# BigBus_Error_rev2.net
KiCad netlist of a schematic drawn in EAGLE
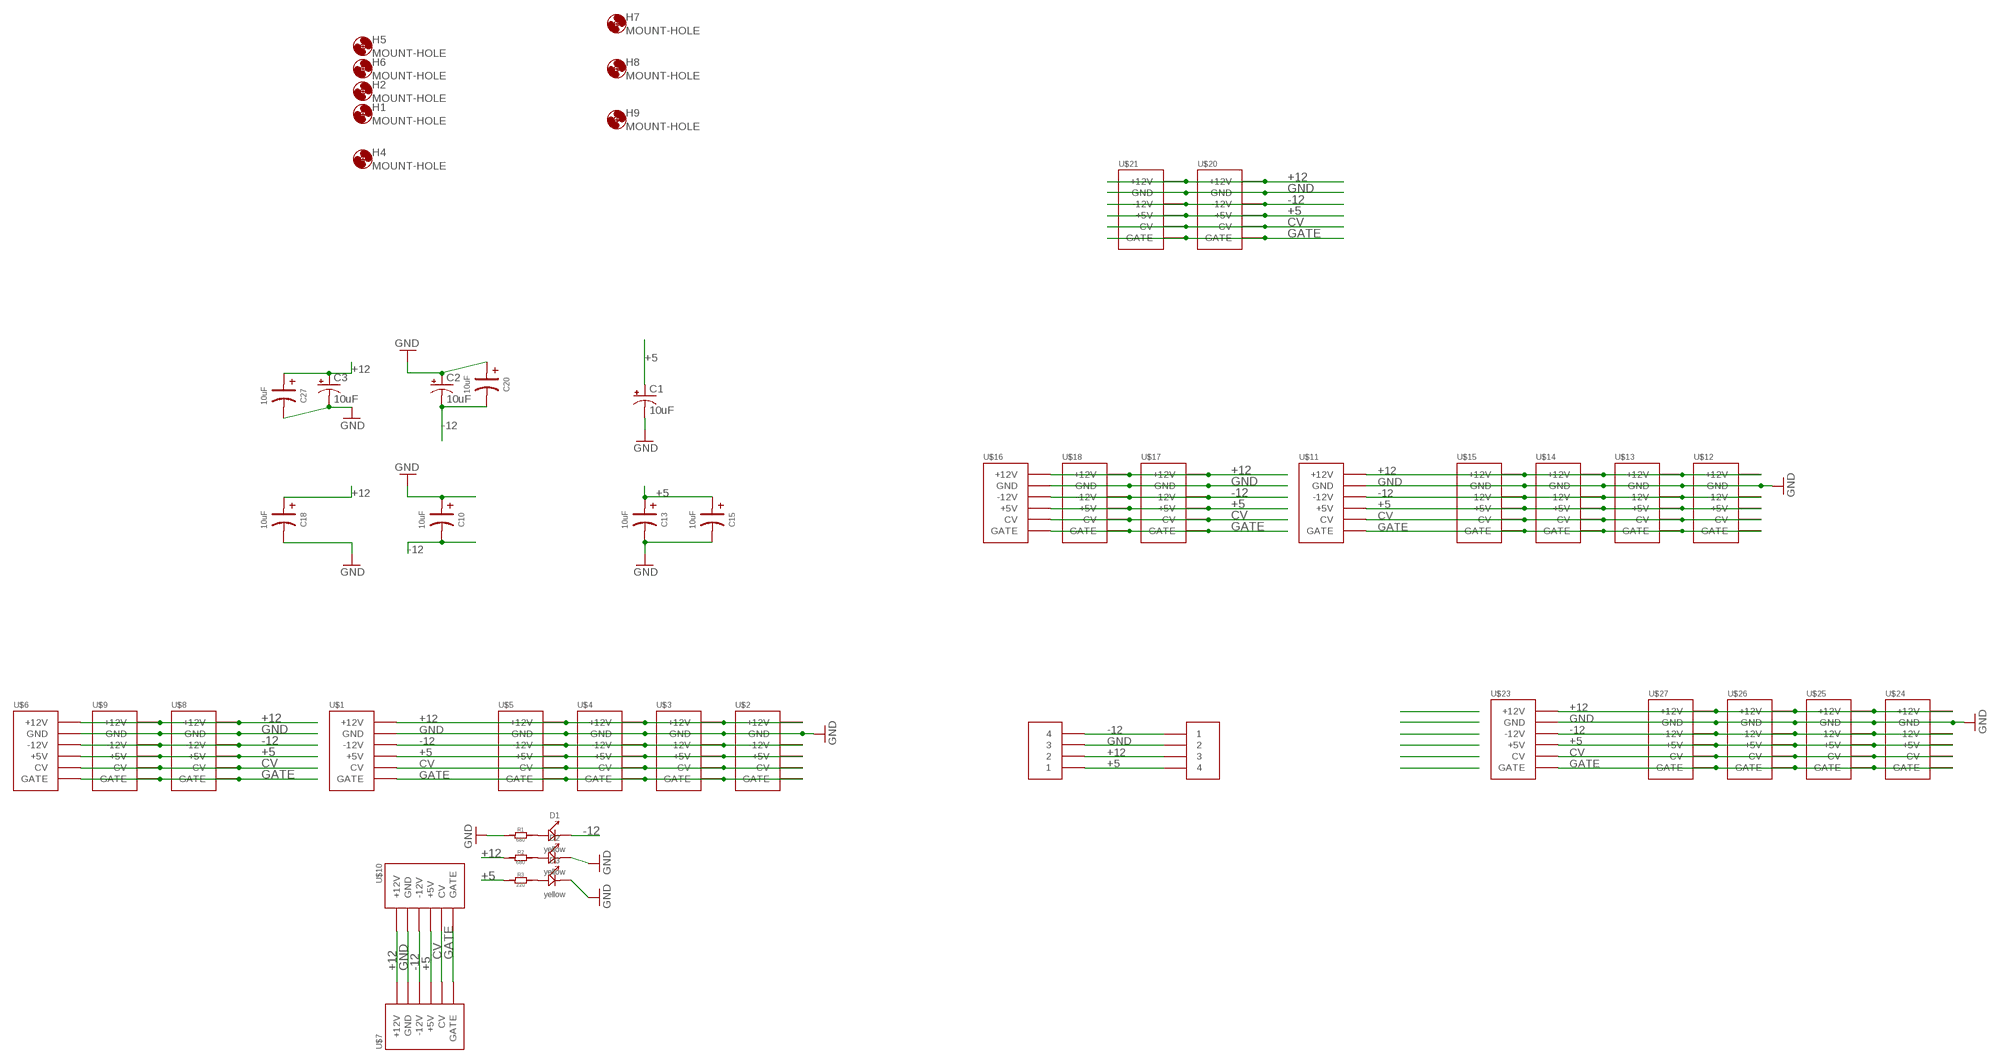
[diagram p0: schematic, sheet 1]

(export (version "E")
  (design (tool "Eeschema 10.0.6"))
  (components
    (comp (ref "C1")
      (value "10uF")
      (footprint "eagle-import:PANASONIC_D")
      (libsource (lib "eagle-import") (part "CAP_POLD"))
    )
    (comp (ref "C2")
      (value "10uF")
      (footprint "eagle-import:PANASONIC_D")
      (libsource (lib "eagle-import") (part "CAP_POLD"))
    )
    (comp (ref "C3")
      (value "10uF")
      (footprint "eagle-import:PANASONIC_D")
      (libsource (lib "eagle-import") (part "CAP_POLD"))
    )
    (comp (ref "C10")
      (value "10uF")
      (footprint "eagle-import:CASE-A_3216")
      (libsource (lib "eagle-import") (part "C-POLAR-A"))
    )
    (comp (ref "C13")
      (value "10uF")
      (footprint "eagle-import:CASE-A_3216")
      (libsource (lib "eagle-import") (part "C-POLAR-A"))
    )
    (comp (ref "C15")
      (value "10uF")
      (footprint "eagle-import:CASE-A_3216")
      (libsource (lib "eagle-import") (part "C-POLAR-A"))
    )
    (comp (ref "C18")
      (value "10uF")
      (footprint "eagle-import:CASE-A_3216")
      (libsource (lib "eagle-import") (part "C-POLAR-A"))
    )
    (comp (ref "C20")
      (value "10uF")
      (footprint "eagle-import:CASE-A_3216")
      (libsource (lib "eagle-import") (part "C-POLAR-A"))
    )
    (comp (ref "C27")
      (value "10uF")
      (footprint "eagle-import:CASE-A_3216")
      (libsource (lib "eagle-import") (part "C-POLAR-A"))
    )
    (comp (ref "D1")
      (value "yellow")
      (footprint "eagle-import:LED0603")
      (libsource (lib "eagle-import") (part "LED"))
    )
    (comp (ref "D2")
      (value "yellow")
      (footprint "eagle-import:LED0603")
      (libsource (lib "eagle-import") (part "LED"))
    )
    (comp (ref "D3")
      (value "yellow")
      (footprint "eagle-import:LED0603")
      (libsource (lib "eagle-import") (part "LED"))
    )
    (comp (ref "H1")
      (value "MOUNT-HOLE")
      (footprint "eagle-import:3.2-NOMARKINGS-SMALLSAFEZONE")
      (libsource (lib "eagle-import") (part "MOUNT-HOLE"))
    )
    (comp (ref "H2")
      (value "MOUNT-HOLE")
      (footprint "eagle-import:3.2-NOMARKINGS-SMALLSAFEZONE")
      (libsource (lib "eagle-import") (part "MOUNT-HOLE"))
    )
    (comp (ref "H4")
      (value "MOUNT-HOLE")
      (footprint "eagle-import:3.2-NOMARKINGS-SMALLSAFEZONE")
      (libsource (lib "eagle-import") (part "MOUNT-HOLE"))
    )
    (comp (ref "H5")
      (value "MOUNT-HOLE")
      (footprint "eagle-import:3.2-NOMARKINGS-SMALLSAFEZONE")
      (libsource (lib "eagle-import") (part "MOUNT-HOLE"))
    )
    (comp (ref "H6")
      (value "MOUNT-HOLE")
      (footprint "eagle-import:3.2-NOMARKINGS-SMALLSAFEZONE")
      (libsource (lib "eagle-import") (part "MOUNT-HOLE"))
    )
    (comp (ref "H7")
      (value "MOUNT-HOLE")
      (footprint "eagle-import:3.2-NOMARKINGS-SMALLSAFEZONE")
      (libsource (lib "eagle-import") (part "MOUNT-HOLE"))
    )
    (comp (ref "H8")
      (value "MOUNT-HOLE")
      (footprint "eagle-import:3.2-NOMARKINGS-SMALLSAFEZONE")
      (libsource (lib "eagle-import") (part "MOUNT-HOLE"))
    )
    (comp (ref "H9")
      (value "MOUNT-HOLE")
      (footprint "eagle-import:3.2-NOMARKINGS-SMALLSAFEZONE")
      (libsource (lib "eagle-import") (part "MOUNT-HOLE"))
    )
    (comp (ref "R1")
      (value "680")
      (footprint "eagle-import:R0603")
      (libsource (lib "eagle-import") (part "R-0603"))
    )
    (comp (ref "R2")
      (value "680")
      (footprint "eagle-import:R0603")
      (libsource (lib "eagle-import") (part "R-0603"))
    )
    (comp (ref "R3")
      (value "220")
      (footprint "eagle-import:R0603")
      (libsource (lib "eagle-import") (part "R-0603"))
    )
    (comp (ref "U$1")
      (value "POWER_SHROUDED_NOTEXT")
      (footprint "eagle-import:POWER_16_SHROUDED_NOTEXT")
      (libsource (lib "eagle-import") (part "POWER_SHROUDED_NOTEXT"))
    )
    (comp (ref "U$2")
      (value "POWER_SHROUDED_NOTEXT")
      (footprint "eagle-import:POWER_16_SHROUDED_NOTEXT")
      (libsource (lib "eagle-import") (part "POWER_SHROUDED_NOTEXT"))
    )
    (comp (ref "U$3")
      (value "POWER_SHROUDED_NOTEXT")
      (footprint "eagle-import:POWER_16_SHROUDED_NOTEXT")
      (libsource (lib "eagle-import") (part "POWER_SHROUDED_NOTEXT"))
    )
    (comp (ref "U$4")
      (value "POWER_SHROUDED_NOTEXT")
      (footprint "eagle-import:POWER_16_SHROUDED_NOTEXT")
      (libsource (lib "eagle-import") (part "POWER_SHROUDED_NOTEXT"))
    )
    (comp (ref "U$5")
      (value "POWER_SHROUDED_NOTEXT")
      (footprint "eagle-import:POWER_16_SHROUDED_NOTEXT")
      (libsource (lib "eagle-import") (part "POWER_SHROUDED_NOTEXT"))
    )
    (comp (ref "U$6")
      (value "POWER_SHROUDED_NOTEXT")
      (footprint "eagle-import:POWER_16_SHROUDED_NOTEXT")
      (libsource (lib "eagle-import") (part "POWER_SHROUDED_NOTEXT"))
    )
    (comp (ref "U$7")
      (value "POWER_SHROUDED_NOTEXT")
      (footprint "eagle-import:POWER_16_SHROUDED_NOTEXT")
      (libsource (lib "eagle-import") (part "POWER_SHROUDED_NOTEXT"))
    )
    (comp (ref "U$8")
      (value "POWER_SHROUDED_NOTEXT")
      (footprint "eagle-import:POWER_16_SHROUDED_NOTEXT")
      (libsource (lib "eagle-import") (part "POWER_SHROUDED_NOTEXT"))
    )
    (comp (ref "U$9")
      (value "POWER_SHROUDED_NOTEXT")
      (footprint "eagle-import:POWER_16_SHROUDED_NOTEXT")
      (libsource (lib "eagle-import") (part "POWER_SHROUDED_NOTEXT"))
    )
    (comp (ref "U$10")
      (value "POWER_SHROUDED_NOTEXT")
      (footprint "eagle-import:POWER_16_SHROUDED_NOTEXT")
      (libsource (lib "eagle-import") (part "POWER_SHROUDED_NOTEXT"))
    )
    (comp (ref "U$11")
      (value "POWER_SHROUDED_NOTEXT")
      (footprint "eagle-import:POWER_16_SHROUDED_NOTEXT")
      (libsource (lib "eagle-import") (part "POWER_SHROUDED_NOTEXT"))
    )
    (comp (ref "U$12")
      (value "POWER_SHROUDED_NOTEXT")
      (footprint "eagle-import:POWER_16_SHROUDED_NOTEXT")
      (libsource (lib "eagle-import") (part "POWER_SHROUDED_NOTEXT"))
    )
    (comp (ref "U$13")
      (value "POWER_SHROUDED_NOTEXT")
      (footprint "eagle-import:POWER_16_SHROUDED_NOTEXT")
      (libsource (lib "eagle-import") (part "POWER_SHROUDED_NOTEXT"))
    )
    (comp (ref "U$14")
      (value "POWER_SHROUDED_NOTEXT")
      (footprint "eagle-import:POWER_16_SHROUDED_NOTEXT")
      (libsource (lib "eagle-import") (part "POWER_SHROUDED_NOTEXT"))
    )
    (comp (ref "U$15")
      (value "POWER_SHROUDED_NOTEXT")
      (footprint "eagle-import:POWER_16_SHROUDED_NOTEXT")
      (libsource (lib "eagle-import") (part "POWER_SHROUDED_NOTEXT"))
    )
    (comp (ref "U$16")
      (value "POWER_SHROUDED_NOTEXT")
      (footprint "eagle-import:POWER_16_SHROUDED_NOTEXT")
      (libsource (lib "eagle-import") (part "POWER_SHROUDED_NOTEXT"))
    )
    (comp (ref "U$17")
      (value "POWER_SHROUDED_NOTEXT")
      (footprint "eagle-import:POWER_16_SHROUDED_NOTEXT")
      (libsource (lib "eagle-import") (part "POWER_SHROUDED_NOTEXT"))
    )
    (comp (ref "U$18")
      (value "POWER_SHROUDED_NOTEXT")
      (footprint "eagle-import:POWER_16_SHROUDED_NOTEXT")
      (libsource (lib "eagle-import") (part "POWER_SHROUDED_NOTEXT"))
    )
    (comp (ref "U$19")
      (value "4PIN5MM")
      (footprint "eagle-import:4PIN5MM")
      (libsource (lib "eagle-import") (part "4PIN5MM"))
    )
    (comp (ref "U$20")
      (value "POWER_SHROUDED_NOTEXT")
      (footprint "eagle-import:POWER_16_SHROUDED_NOTEXT")
      (libsource (lib "eagle-import") (part "POWER_SHROUDED_NOTEXT"))
    )
    (comp (ref "U$21")
      (value "POWER_SHROUDED_NOTEXT")
      (footprint "eagle-import:POWER_16_SHROUDED_NOTEXT")
      (libsource (lib "eagle-import") (part "POWER_SHROUDED_NOTEXT"))
    )
    (comp (ref "U$22")
      (value "4PIN5MM")
      (footprint "eagle-import:4PIN5MM")
      (libsource (lib "eagle-import") (part "4PIN5MM"))
    )
    (comp (ref "U$23")
      (value "POWER_SHROUDED_NOTEXT")
      (footprint "eagle-import:POWER_16_SHROUDED_NOTEXT")
      (libsource (lib "eagle-import") (part "POWER_SHROUDED_NOTEXT"))
    )
    (comp (ref "U$24")
      (value "POWER_SHROUDED_NOTEXT")
      (footprint "eagle-import:POWER_16_SHROUDED_NOTEXT")
      (libsource (lib "eagle-import") (part "POWER_SHROUDED_NOTEXT"))
    )
    (comp (ref "U$25")
      (value "POWER_SHROUDED_NOTEXT")
      (footprint "eagle-import:POWER_16_SHROUDED_NOTEXT")
      (libsource (lib "eagle-import") (part "POWER_SHROUDED_NOTEXT"))
    )
    (comp (ref "U$26")
      (value "POWER_SHROUDED_NOTEXT")
      (footprint "eagle-import:POWER_16_SHROUDED_NOTEXT")
      (libsource (lib "eagle-import") (part "POWER_SHROUDED_NOTEXT"))
    )
    (comp (ref "U$27")
      (value "POWER_SHROUDED_NOTEXT")
      (footprint "eagle-import:POWER_16_SHROUDED_NOTEXT")
      (libsource (lib "eagle-import") (part "POWER_SHROUDED_NOTEXT"))
    )
  )
  (nets
    (net (code "1") (name "/+5") (class "Default")
      (node (ref "C1") (pin "+") (pinfunction "+_+") (pintype "passive"))
      (node (ref "C13") (pin "+") (pinfunction "1_+") (pintype "bidirectional"))
      (node (ref "C15") (pin "+") (pinfunction "1_+") (pintype "bidirectional"))
      (node (ref "R3") (pin "1") (pinfunction "1_1") (pintype "bidirectional"))
      (node (ref "U$1") (pin "11") (pinfunction "+5V_11") (pintype "bidirectional"))
      (node (ref "U$1") (pin "12") (pinfunction "+5V_12") (pintype "bidirectional"))
      (node (ref "U$10") (pin "11") (pinfunction "+5V_11") (pintype "bidirectional"))
      (node (ref "U$10") (pin "12") (pinfunction "+5V_12") (pintype "bidirectional"))
      (node (ref "U$11") (pin "11") (pinfunction "+5V_11") (pintype "bidirectional"))
      (node (ref "U$11") (pin "12") (pinfunction "+5V_12") (pintype "bidirectional"))
      (node (ref "U$12") (pin "11") (pinfunction "+5V_11") (pintype "bidirectional"))
      (node (ref "U$12") (pin "12") (pinfunction "+5V_12") (pintype "bidirectional"))
      (node (ref "U$13") (pin "11") (pinfunction "+5V_11") (pintype "bidirectional"))
      (node (ref "U$13") (pin "12") (pinfunction "+5V_12") (pintype "bidirectional"))
      (node (ref "U$14") (pin "11") (pinfunction "+5V_11") (pintype "bidirectional"))
      (node (ref "U$14") (pin "12") (pinfunction "+5V_12") (pintype "bidirectional"))
      (node (ref "U$15") (pin "11") (pinfunction "+5V_11") (pintype "bidirectional"))
      (node (ref "U$15") (pin "12") (pinfunction "+5V_12") (pintype "bidirectional"))
      (node (ref "U$16") (pin "11") (pinfunction "+5V_11") (pintype "bidirectional"))
      (node (ref "U$16") (pin "12") (pinfunction "+5V_12") (pintype "bidirectional"))
      (node (ref "U$17") (pin "11") (pinfunction "+5V_11") (pintype "bidirectional"))
      (node (ref "U$17") (pin "12") (pinfunction "+5V_12") (pintype "bidirectional"))
      (node (ref "U$18") (pin "11") (pinfunction "+5V_11") (pintype "bidirectional"))
      (node (ref "U$18") (pin "12") (pinfunction "+5V_12") (pintype "bidirectional"))
      (node (ref "U$19") (pin "4") (pinfunction "4_4") (pintype "bidirectional"))
      (node (ref "U$2") (pin "11") (pinfunction "+5V_11") (pintype "bidirectional"))
      (node (ref "U$2") (pin "12") (pinfunction "+5V_12") (pintype "bidirectional"))
      (node (ref "U$20") (pin "11") (pinfunction "+5V_11") (pintype "bidirectional"))
      (node (ref "U$20") (pin "12") (pinfunction "+5V_12") (pintype "bidirectional"))
      (node (ref "U$21") (pin "11") (pinfunction "+5V_11") (pintype "bidirectional"))
      (node (ref "U$21") (pin "12") (pinfunction "+5V_12") (pintype "bidirectional"))
      (node (ref "U$22") (pin "1") (pinfunction "1_1") (pintype "bidirectional"))
      (node (ref "U$23") (pin "11") (pinfunction "+5V_11") (pintype "bidirectional"))
      (node (ref "U$23") (pin "12") (pinfunction "+5V_12") (pintype "bidirectional"))
      (node (ref "U$24") (pin "11") (pinfunction "+5V_11") (pintype "bidirectional"))
      (node (ref "U$24") (pin "12") (pinfunction "+5V_12") (pintype "bidirectional"))
      (node (ref "U$25") (pin "11") (pinfunction "+5V_11") (pintype "bidirectional"))
      (node (ref "U$25") (pin "12") (pinfunction "+5V_12") (pintype "bidirectional"))
      (node (ref "U$26") (pin "11") (pinfunction "+5V_11") (pintype "bidirectional"))
      (node (ref "U$26") (pin "12") (pinfunction "+5V_12") (pintype "bidirectional"))
      (node (ref "U$27") (pin "11") (pinfunction "+5V_11") (pintype "bidirectional"))
      (node (ref "U$27") (pin "12") (pinfunction "+5V_12") (pintype "bidirectional"))
      (node (ref "U$3") (pin "11") (pinfunction "+5V_11") (pintype "bidirectional"))
      (node (ref "U$3") (pin "12") (pinfunction "+5V_12") (pintype "bidirectional"))
      (node (ref "U$4") (pin "11") (pinfunction "+5V_11") (pintype "bidirectional"))
      (node (ref "U$4") (pin "12") (pinfunction "+5V_12") (pintype "bidirectional"))
      (node (ref "U$5") (pin "11") (pinfunction "+5V_11") (pintype "bidirectional"))
      (node (ref "U$5") (pin "12") (pinfunction "+5V_12") (pintype "bidirectional"))
      (node (ref "U$6") (pin "11") (pinfunction "+5V_11") (pintype "bidirectional"))
      (node (ref "U$6") (pin "12") (pinfunction "+5V_12") (pintype "bidirectional"))
      (node (ref "U$7") (pin "11") (pinfunction "+5V_11") (pintype "bidirectional"))
      (node (ref "U$7") (pin "12") (pinfunction "+5V_12") (pintype "bidirectional"))
      (node (ref "U$8") (pin "11") (pinfunction "+5V_11") (pintype "bidirectional"))
      (node (ref "U$8") (pin "12") (pinfunction "+5V_12") (pintype "bidirectional"))
      (node (ref "U$9") (pin "11") (pinfunction "+5V_11") (pintype "bidirectional"))
      (node (ref "U$9") (pin "12") (pinfunction "+5V_12") (pintype "bidirectional"))
    )
    (net (code "2") (name "/+12") (class "Default")
      (node (ref "C18") (pin "+") (pinfunction "1_+") (pintype "bidirectional"))
      (node (ref "C27") (pin "+") (pinfunction "1_+") (pintype "bidirectional"))
      (node (ref "C3") (pin "+") (pinfunction "+_+") (pintype "passive"))
      (node (ref "R2") (pin "1") (pinfunction "1_1") (pintype "bidirectional"))
      (node (ref "U$1") (pin "10") (pinfunction "+12V_10") (pintype "bidirectional"))
      (node (ref "U$1") (pin "9") (pinfunction "+12V_9") (pintype "bidirectional"))
      (node (ref "U$10") (pin "10") (pinfunction "+12V_10") (pintype "bidirectional"))
      (node (ref "U$10") (pin "9") (pinfunction "+12V_9") (pintype "bidirectional"))
      (node (ref "U$11") (pin "10") (pinfunction "+12V_10") (pintype "bidirectional"))
      (node (ref "U$11") (pin "9") (pinfunction "+12V_9") (pintype "bidirectional"))
      (node (ref "U$12") (pin "10") (pinfunction "+12V_10") (pintype "bidirectional"))
      (node (ref "U$12") (pin "9") (pinfunction "+12V_9") (pintype "bidirectional"))
      (node (ref "U$13") (pin "10") (pinfunction "+12V_10") (pintype "bidirectional"))
      (node (ref "U$13") (pin "9") (pinfunction "+12V_9") (pintype "bidirectional"))
      (node (ref "U$14") (pin "10") (pinfunction "+12V_10") (pintype "bidirectional"))
      (node (ref "U$14") (pin "9") (pinfunction "+12V_9") (pintype "bidirectional"))
      (node (ref "U$15") (pin "10") (pinfunction "+12V_10") (pintype "bidirectional"))
      (node (ref "U$15") (pin "9") (pinfunction "+12V_9") (pintype "bidirectional"))
      (node (ref "U$16") (pin "10") (pinfunction "+12V_10") (pintype "bidirectional"))
      (node (ref "U$16") (pin "9") (pinfunction "+12V_9") (pintype "bidirectional"))
      (node (ref "U$17") (pin "10") (pinfunction "+12V_10") (pintype "bidirectional"))
      (node (ref "U$17") (pin "9") (pinfunction "+12V_9") (pintype "bidirectional"))
      (node (ref "U$18") (pin "10") (pinfunction "+12V_10") (pintype "bidirectional"))
      (node (ref "U$18") (pin "9") (pinfunction "+12V_9") (pintype "bidirectional"))
      (node (ref "U$19") (pin "3") (pinfunction "3_3") (pintype "bidirectional"))
      (node (ref "U$2") (pin "10") (pinfunction "+12V_10") (pintype "bidirectional"))
      (node (ref "U$2") (pin "9") (pinfunction "+12V_9") (pintype "bidirectional"))
      (node (ref "U$20") (pin "10") (pinfunction "+12V_10") (pintype "bidirectional"))
      (node (ref "U$20") (pin "9") (pinfunction "+12V_9") (pintype "bidirectional"))
      (node (ref "U$21") (pin "10") (pinfunction "+12V_10") (pintype "bidirectional"))
      (node (ref "U$21") (pin "9") (pinfunction "+12V_9") (pintype "bidirectional"))
      (node (ref "U$22") (pin "2") (pinfunction "2_2") (pintype "bidirectional"))
      (node (ref "U$23") (pin "10") (pinfunction "+12V_10") (pintype "bidirectional"))
      (node (ref "U$23") (pin "9") (pinfunction "+12V_9") (pintype "bidirectional"))
      (node (ref "U$24") (pin "10") (pinfunction "+12V_10") (pintype "bidirectional"))
      (node (ref "U$24") (pin "9") (pinfunction "+12V_9") (pintype "bidirectional"))
      (node (ref "U$25") (pin "10") (pinfunction "+12V_10") (pintype "bidirectional"))
      (node (ref "U$25") (pin "9") (pinfunction "+12V_9") (pintype "bidirectional"))
      (node (ref "U$26") (pin "10") (pinfunction "+12V_10") (pintype "bidirectional"))
      (node (ref "U$26") (pin "9") (pinfunction "+12V_9") (pintype "bidirectional"))
      (node (ref "U$27") (pin "10") (pinfunction "+12V_10") (pintype "bidirectional"))
      (node (ref "U$27") (pin "9") (pinfunction "+12V_9") (pintype "bidirectional"))
      (node (ref "U$3") (pin "10") (pinfunction "+12V_10") (pintype "bidirectional"))
      (node (ref "U$3") (pin "9") (pinfunction "+12V_9") (pintype "bidirectional"))
      (node (ref "U$4") (pin "10") (pinfunction "+12V_10") (pintype "bidirectional"))
      (node (ref "U$4") (pin "9") (pinfunction "+12V_9") (pintype "bidirectional"))
      (node (ref "U$5") (pin "10") (pinfunction "+12V_10") (pintype "bidirectional"))
      (node (ref "U$5") (pin "9") (pinfunction "+12V_9") (pintype "bidirectional"))
      (node (ref "U$6") (pin "10") (pinfunction "+12V_10") (pintype "bidirectional"))
      (node (ref "U$6") (pin "9") (pinfunction "+12V_9") (pintype "bidirectional"))
      (node (ref "U$7") (pin "10") (pinfunction "+12V_10") (pintype "bidirectional"))
      (node (ref "U$7") (pin "9") (pinfunction "+12V_9") (pintype "bidirectional"))
      (node (ref "U$8") (pin "10") (pinfunction "+12V_10") (pintype "bidirectional"))
      (node (ref "U$8") (pin "9") (pinfunction "+12V_9") (pintype "bidirectional"))
      (node (ref "U$9") (pin "10") (pinfunction "+12V_10") (pintype "bidirectional"))
      (node (ref "U$9") (pin "9") (pinfunction "+12V_9") (pintype "bidirectional"))
    )
    (net (code "3") (name "/-12") (class "Default")
      (node (ref "C10") (pin "-") (pinfunction "2_-") (pintype "bidirectional"))
      (node (ref "C2") (pin "-") (pinfunction "-_-") (pintype "passive"))
      (node (ref "C20") (pin "-") (pinfunction "2_-") (pintype "bidirectional"))
      (node (ref "D1") (pin "-") (pinfunction "-_-") (pintype "passive"))
      (node (ref "U$1") (pin "1") (pinfunction "-12V_1") (pintype "bidirectional"))
      (node (ref "U$1") (pin "2") (pinfunction "-12V_2") (pintype "bidirectional"))
      (node (ref "U$10") (pin "1") (pinfunction "-12V_1") (pintype "bidirectional"))
      (node (ref "U$10") (pin "2") (pinfunction "-12V_2") (pintype "bidirectional"))
      (node (ref "U$11") (pin "1") (pinfunction "-12V_1") (pintype "bidirectional"))
      (node (ref "U$11") (pin "2") (pinfunction "-12V_2") (pintype "bidirectional"))
      (node (ref "U$12") (pin "1") (pinfunction "-12V_1") (pintype "bidirectional"))
      (node (ref "U$12") (pin "2") (pinfunction "-12V_2") (pintype "bidirectional"))
      (node (ref "U$13") (pin "1") (pinfunction "-12V_1") (pintype "bidirectional"))
      (node (ref "U$13") (pin "2") (pinfunction "-12V_2") (pintype "bidirectional"))
      (node (ref "U$14") (pin "1") (pinfunction "-12V_1") (pintype "bidirectional"))
      (node (ref "U$14") (pin "2") (pinfunction "-12V_2") (pintype "bidirectional"))
      (node (ref "U$15") (pin "1") (pinfunction "-12V_1") (pintype "bidirectional"))
      (node (ref "U$15") (pin "2") (pinfunction "-12V_2") (pintype "bidirectional"))
      (node (ref "U$16") (pin "1") (pinfunction "-12V_1") (pintype "bidirectional"))
      (node (ref "U$16") (pin "2") (pinfunction "-12V_2") (pintype "bidirectional"))
      (node (ref "U$17") (pin "1") (pinfunction "-12V_1") (pintype "bidirectional"))
      (node (ref "U$17") (pin "2") (pinfunction "-12V_2") (pintype "bidirectional"))
      (node (ref "U$18") (pin "1") (pinfunction "-12V_1") (pintype "bidirectional"))
      (node (ref "U$18") (pin "2") (pinfunction "-12V_2") (pintype "bidirectional"))
      (node (ref "U$19") (pin "1") (pinfunction "1_1") (pintype "bidirectional"))
      (node (ref "U$2") (pin "1") (pinfunction "-12V_1") (pintype "bidirectional"))
      (node (ref "U$2") (pin "2") (pinfunction "-12V_2") (pintype "bidirectional"))
      (node (ref "U$20") (pin "1") (pinfunction "-12V_1") (pintype "bidirectional"))
      (node (ref "U$20") (pin "2") (pinfunction "-12V_2") (pintype "bidirectional"))
      (node (ref "U$21") (pin "1") (pinfunction "-12V_1") (pintype "bidirectional"))
      (node (ref "U$21") (pin "2") (pinfunction "-12V_2") (pintype "bidirectional"))
      (node (ref "U$22") (pin "4") (pinfunction "4_4") (pintype "bidirectional"))
      (node (ref "U$23") (pin "1") (pinfunction "-12V_1") (pintype "bidirectional"))
      (node (ref "U$23") (pin "2") (pinfunction "-12V_2") (pintype "bidirectional"))
      (node (ref "U$24") (pin "1") (pinfunction "-12V_1") (pintype "bidirectional"))
      (node (ref "U$24") (pin "2") (pinfunction "-12V_2") (pintype "bidirectional"))
      (node (ref "U$25") (pin "1") (pinfunction "-12V_1") (pintype "bidirectional"))
      (node (ref "U$25") (pin "2") (pinfunction "-12V_2") (pintype "bidirectional"))
      (node (ref "U$26") (pin "1") (pinfunction "-12V_1") (pintype "bidirectional"))
      (node (ref "U$26") (pin "2") (pinfunction "-12V_2") (pintype "bidirectional"))
      (node (ref "U$27") (pin "1") (pinfunction "-12V_1") (pintype "bidirectional"))
      (node (ref "U$27") (pin "2") (pinfunction "-12V_2") (pintype "bidirectional"))
      (node (ref "U$3") (pin "1") (pinfunction "-12V_1") (pintype "bidirectional"))
      (node (ref "U$3") (pin "2") (pinfunction "-12V_2") (pintype "bidirectional"))
      (node (ref "U$4") (pin "1") (pinfunction "-12V_1") (pintype "bidirectional"))
      (node (ref "U$4") (pin "2") (pinfunction "-12V_2") (pintype "bidirectional"))
      (node (ref "U$5") (pin "1") (pinfunction "-12V_1") (pintype "bidirectional"))
      (node (ref "U$5") (pin "2") (pinfunction "-12V_2") (pintype "bidirectional"))
      (node (ref "U$6") (pin "1") (pinfunction "-12V_1") (pintype "bidirectional"))
      (node (ref "U$6") (pin "2") (pinfunction "-12V_2") (pintype "bidirectional"))
      (node (ref "U$7") (pin "1") (pinfunction "-12V_1") (pintype "bidirectional"))
      (node (ref "U$7") (pin "2") (pinfunction "-12V_2") (pintype "bidirectional"))
      (node (ref "U$8") (pin "1") (pinfunction "-12V_1") (pintype "bidirectional"))
      (node (ref "U$8") (pin "2") (pinfunction "-12V_2") (pintype "bidirectional"))
      (node (ref "U$9") (pin "1") (pinfunction "-12V_1") (pintype "bidirectional"))
      (node (ref "U$9") (pin "2") (pinfunction "-12V_2") (pintype "bidirectional"))
    )
    (net (code "4") (name "/CV") (class "Default")
      (node (ref "U$1") (pin "13") (pinfunction "CV_13") (pintype "bidirectional"))
      (node (ref "U$1") (pin "14") (pinfunction "CV_14") (pintype "bidirectional"))
      (node (ref "U$10") (pin "13") (pinfunction "CV_13") (pintype "bidirectional"))
      (node (ref "U$10") (pin "14") (pinfunction "CV_14") (pintype "bidirectional"))
      (node (ref "U$11") (pin "13") (pinfunction "CV_13") (pintype "bidirectional"))
      (node (ref "U$11") (pin "14") (pinfunction "CV_14") (pintype "bidirectional"))
      (node (ref "U$12") (pin "13") (pinfunction "CV_13") (pintype "bidirectional"))
      (node (ref "U$12") (pin "14") (pinfunction "CV_14") (pintype "bidirectional"))
      (node (ref "U$13") (pin "13") (pinfunction "CV_13") (pintype "bidirectional"))
      (node (ref "U$13") (pin "14") (pinfunction "CV_14") (pintype "bidirectional"))
      (node (ref "U$14") (pin "13") (pinfunction "CV_13") (pintype "bidirectional"))
      (node (ref "U$14") (pin "14") (pinfunction "CV_14") (pintype "bidirectional"))
      (node (ref "U$15") (pin "13") (pinfunction "CV_13") (pintype "bidirectional"))
      (node (ref "U$15") (pin "14") (pinfunction "CV_14") (pintype "bidirectional"))
      (node (ref "U$16") (pin "13") (pinfunction "CV_13") (pintype "bidirectional"))
      (node (ref "U$16") (pin "14") (pinfunction "CV_14") (pintype "bidirectional"))
      (node (ref "U$17") (pin "13") (pinfunction "CV_13") (pintype "bidirectional"))
      (node (ref "U$17") (pin "14") (pinfunction "CV_14") (pintype "bidirectional"))
      (node (ref "U$18") (pin "13") (pinfunction "CV_13") (pintype "bidirectional"))
      (node (ref "U$18") (pin "14") (pinfunction "CV_14") (pintype "bidirectional"))
      (node (ref "U$2") (pin "13") (pinfunction "CV_13") (pintype "bidirectional"))
      (node (ref "U$2") (pin "14") (pinfunction "CV_14") (pintype "bidirectional"))
      (node (ref "U$20") (pin "13") (pinfunction "CV_13") (pintype "bidirectional"))
      (node (ref "U$20") (pin "14") (pinfunction "CV_14") (pintype "bidirectional"))
      (node (ref "U$21") (pin "13") (pinfunction "CV_13") (pintype "bidirectional"))
      (node (ref "U$21") (pin "14") (pinfunction "CV_14") (pintype "bidirectional"))
      (node (ref "U$23") (pin "13") (pinfunction "CV_13") (pintype "bidirectional"))
      (node (ref "U$23") (pin "14") (pinfunction "CV_14") (pintype "bidirectional"))
      (node (ref "U$24") (pin "13") (pinfunction "CV_13") (pintype "bidirectional"))
      (node (ref "U$24") (pin "14") (pinfunction "CV_14") (pintype "bidirectional"))
      (node (ref "U$25") (pin "13") (pinfunction "CV_13") (pintype "bidirectional"))
      (node (ref "U$25") (pin "14") (pinfunction "CV_14") (pintype "bidirectional"))
      (node (ref "U$26") (pin "13") (pinfunction "CV_13") (pintype "bidirectional"))
      (node (ref "U$26") (pin "14") (pinfunction "CV_14") (pintype "bidirectional"))
      (node (ref "U$27") (pin "13") (pinfunction "CV_13") (pintype "bidirectional"))
      (node (ref "U$27") (pin "14") (pinfunction "CV_14") (pintype "bidirectional"))
      (node (ref "U$3") (pin "13") (pinfunction "CV_13") (pintype "bidirectional"))
      (node (ref "U$3") (pin "14") (pinfunction "CV_14") (pintype "bidirectional"))
      (node (ref "U$4") (pin "13") (pinfunction "CV_13") (pintype "bidirectional"))
      (node (ref "U$4") (pin "14") (pinfunction "CV_14") (pintype "bidirectional"))
      (node (ref "U$5") (pin "13") (pinfunction "CV_13") (pintype "bidirectional"))
      (node (ref "U$5") (pin "14") (pinfunction "CV_14") (pintype "bidirectional"))
      (node (ref "U$6") (pin "13") (pinfunction "CV_13") (pintype "bidirectional"))
      (node (ref "U$6") (pin "14") (pinfunction "CV_14") (pintype "bidirectional"))
      (node (ref "U$7") (pin "13") (pinfunction "CV_13") (pintype "bidirectional"))
      (node (ref "U$7") (pin "14") (pinfunction "CV_14") (pintype "bidirectional"))
      (node (ref "U$8") (pin "13") (pinfunction "CV_13") (pintype "bidirectional"))
      (node (ref "U$8") (pin "14") (pinfunction "CV_14") (pintype "bidirectional"))
      (node (ref "U$9") (pin "13") (pinfunction "CV_13") (pintype "bidirectional"))
      (node (ref "U$9") (pin "14") (pinfunction "CV_14") (pintype "bidirectional"))
    )
    (net (code "5") (name "/GATE") (class "Default")
      (node (ref "U$1") (pin "15") (pinfunction "GATE_15") (pintype "bidirectional"))
      (node (ref "U$1") (pin "16") (pinfunction "GATE_16") (pintype "bidirectional"))
      (node (ref "U$10") (pin "15") (pinfunction "GATE_15") (pintype "bidirectional"))
      (node (ref "U$10") (pin "16") (pinfunction "GATE_16") (pintype "bidirectional"))
      (node (ref "U$11") (pin "15") (pinfunction "GATE_15") (pintype "bidirectional"))
      (node (ref "U$11") (pin "16") (pinfunction "GATE_16") (pintype "bidirectional"))
      (node (ref "U$12") (pin "15") (pinfunction "GATE_15") (pintype "bidirectional"))
      (node (ref "U$12") (pin "16") (pinfunction "GATE_16") (pintype "bidirectional"))
      (node (ref "U$13") (pin "15") (pinfunction "GATE_15") (pintype "bidirectional"))
      (node (ref "U$13") (pin "16") (pinfunction "GATE_16") (pintype "bidirectional"))
      (node (ref "U$14") (pin "15") (pinfunction "GATE_15") (pintype "bidirectional"))
      (node (ref "U$14") (pin "16") (pinfunction "GATE_16") (pintype "bidirectional"))
      (node (ref "U$15") (pin "15") (pinfunction "GATE_15") (pintype "bidirectional"))
      (node (ref "U$15") (pin "16") (pinfunction "GATE_16") (pintype "bidirectional"))
      (node (ref "U$16") (pin "15") (pinfunction "GATE_15") (pintype "bidirectional"))
      (node (ref "U$16") (pin "16") (pinfunction "GATE_16") (pintype "bidirectional"))
      (node (ref "U$17") (pin "15") (pinfunction "GATE_15") (pintype "bidirectional"))
      (node (ref "U$17") (pin "16") (pinfunction "GATE_16") (pintype "bidirectional"))
      (node (ref "U$18") (pin "15") (pinfunction "GATE_15") (pintype "bidirectional"))
      (node (ref "U$18") (pin "16") (pinfunction "GATE_16") (pintype "bidirectional"))
      (node (ref "U$2") (pin "15") (pinfunction "GATE_15") (pintype "bidirectional"))
      (node (ref "U$2") (pin "16") (pinfunction "GATE_16") (pintype "bidirectional"))
      (node (ref "U$20") (pin "15") (pinfunction "GATE_15") (pintype "bidirectional"))
      (node (ref "U$20") (pin "16") (pinfunction "GATE_16") (pintype "bidirectional"))
      (node (ref "U$21") (pin "15") (pinfunction "GATE_15") (pintype "bidirectional"))
      (node (ref "U$21") (pin "16") (pinfunction "GATE_16") (pintype "bidirectional"))
      (node (ref "U$23") (pin "15") (pinfunction "GATE_15") (pintype "bidirectional"))
      (node (ref "U$23") (pin "16") (pinfunction "GATE_16") (pintype "bidirectional"))
      (node (ref "U$24") (pin "15") (pinfunction "GATE_15") (pintype "bidirectional"))
      (node (ref "U$24") (pin "16") (pinfunction "GATE_16") (pintype "bidirectional"))
      (node (ref "U$25") (pin "15") (pinfunction "GATE_15") (pintype "bidirectional"))
      (node (ref "U$25") (pin "16") (pinfunction "GATE_16") (pintype "bidirectional"))
      (node (ref "U$26") (pin "15") (pinfunction "GATE_15") (pintype "bidirectional"))
      (node (ref "U$26") (pin "16") (pinfunction "GATE_16") (pintype "bidirectional"))
      (node (ref "U$27") (pin "15") (pinfunction "GATE_15") (pintype "bidirectional"))
      (node (ref "U$27") (pin "16") (pinfunction "GATE_16") (pintype "bidirectional"))
      (node (ref "U$3") (pin "15") (pinfunction "GATE_15") (pintype "bidirectional"))
      (node (ref "U$3") (pin "16") (pinfunction "GATE_16") (pintype "bidirectional"))
      (node (ref "U$4") (pin "15") (pinfunction "GATE_15") (pintype "bidirectional"))
      (node (ref "U$4") (pin "16") (pinfunction "GATE_16") (pintype "bidirectional"))
      (node (ref "U$5") (pin "15") (pinfunction "GATE_15") (pintype "bidirectional"))
      (node (ref "U$5") (pin "16") (pinfunction "GATE_16") (pintype "bidirectional"))
      (node (ref "U$6") (pin "15") (pinfunction "GATE_15") (pintype "bidirectional"))
      (node (ref "U$6") (pin "16") (pinfunction "GATE_16") (pintype "bidirectional"))
      (node (ref "U$7") (pin "15") (pinfunction "GATE_15") (pintype "bidirectional"))
      (node (ref "U$7") (pin "16") (pinfunction "GATE_16") (pintype "bidirectional"))
      (node (ref "U$8") (pin "15") (pinfunction "GATE_15") (pintype "bidirectional"))
      (node (ref "U$8") (pin "16") (pinfunction "GATE_16") (pintype "bidirectional"))
      (node (ref "U$9") (pin "15") (pinfunction "GATE_15") (pintype "bidirectional"))
      (node (ref "U$9") (pin "16") (pinfunction "GATE_16") (pintype "bidirectional"))
    )
    (net (code "6") (name "GND") (class "Default")
      (node (ref "C1") (pin "-") (pinfunction "-_-") (pintype "passive"))
      (node (ref "C10") (pin "+") (pinfunction "1_+") (pintype "bidirectional"))
      (node (ref "C13") (pin "-") (pinfunction "2_-") (pintype "bidirectional"))
      (node (ref "C15") (pin "-") (pinfunction "2_-") (pintype "bidirectional"))
      (node (ref "C18") (pin "-") (pinfunction "2_-") (pintype "bidirectional"))
      (node (ref "C2") (pin "+") (pinfunction "+_+") (pintype "passive"))
      (node (ref "C20") (pin "+") (pinfunction "1_+") (pintype "bidirectional"))
      (node (ref "C27") (pin "-") (pinfunction "2_-") (pintype "bidirectional"))
      (node (ref "C3") (pin "-") (pinfunction "-_-") (pintype "passive"))
      (node (ref "D2") (pin "-") (pinfunction "-_-") (pintype "passive"))
      (node (ref "D3") (pin "-") (pinfunction "-_-") (pintype "passive"))
      (node (ref "R1") (pin "1") (pinfunction "1_1") (pintype "bidirectional"))
      (node (ref "U$1") (pin "3") (pinfunction "GND_3") (pintype "bidirectional"))
      (node (ref "U$1") (pin "4") (pinfunction "GND_4") (pintype "bidirectional"))
      (node (ref "U$1") (pin "5") (pinfunction "GND_5") (pintype "bidirectional"))
      (node (ref "U$1") (pin "6") (pinfunction "GND_6") (pintype "bidirectional"))
      (node (ref "U$1") (pin "7") (pinfunction "GND_7") (pintype "bidirectional"))
      (node (ref "U$1") (pin "8") (pinfunction "GND_8") (pintype "bidirectional"))
      (node (ref "U$10") (pin "3") (pinfunction "GND_3") (pintype "bidirectional"))
      (node (ref "U$10") (pin "4") (pinfunction "GND_4") (pintype "bidirectional"))
      (node (ref "U$10") (pin "5") (pinfunction "GND_5") (pintype "bidirectional"))
      (node (ref "U$10") (pin "6") (pinfunction "GND_6") (pintype "bidirectional"))
      (node (ref "U$10") (pin "7") (pinfunction "GND_7") (pintype "bidirectional"))
      (node (ref "U$10") (pin "8") (pinfunction "GND_8") (pintype "bidirectional"))
      (node (ref "U$11") (pin "3") (pinfunction "GND_3") (pintype "bidirectional"))
      (node (ref "U$11") (pin "4") (pinfunction "GND_4") (pintype "bidirectional"))
      (node (ref "U$11") (pin "5") (pinfunction "GND_5") (pintype "bidirectional"))
      (node (ref "U$11") (pin "6") (pinfunction "GND_6") (pintype "bidirectional"))
      (node (ref "U$11") (pin "7") (pinfunction "GND_7") (pintype "bidirectional"))
      (node (ref "U$11") (pin "8") (pinfunction "GND_8") (pintype "bidirectional"))
      (node (ref "U$12") (pin "3") (pinfunction "GND_3") (pintype "bidirectional"))
      (node (ref "U$12") (pin "4") (pinfunction "GND_4") (pintype "bidirectional"))
      (node (ref "U$12") (pin "5") (pinfunction "GND_5") (pintype "bidirectional"))
      (node (ref "U$12") (pin "6") (pinfunction "GND_6") (pintype "bidirectional"))
      (node (ref "U$12") (pin "7") (pinfunction "GND_7") (pintype "bidirectional"))
      (node (ref "U$12") (pin "8") (pinfunction "GND_8") (pintype "bidirectional"))
      (node (ref "U$13") (pin "3") (pinfunction "GND_3") (pintype "bidirectional"))
      (node (ref "U$13") (pin "4") (pinfunction "GND_4") (pintype "bidirectional"))
      (node (ref "U$13") (pin "5") (pinfunction "GND_5") (pintype "bidirectional"))
      (node (ref "U$13") (pin "6") (pinfunction "GND_6") (pintype "bidirectional"))
      (node (ref "U$13") (pin "7") (pinfunction "GND_7") (pintype "bidirectional"))
      (node (ref "U$13") (pin "8") (pinfunction "GND_8") (pintype "bidirectional"))
      (node (ref "U$14") (pin "3") (pinfunction "GND_3") (pintype "bidirectional"))
      (node (ref "U$14") (pin "4") (pinfunction "GND_4") (pintype "bidirectional"))
      (node (ref "U$14") (pin "5") (pinfunction "GND_5") (pintype "bidirectional"))
      (node (ref "U$14") (pin "6") (pinfunction "GND_6") (pintype "bidirectional"))
      (node (ref "U$14") (pin "7") (pinfunction "GND_7") (pintype "bidirectional"))
      (node (ref "U$14") (pin "8") (pinfunction "GND_8") (pintype "bidirectional"))
      (node (ref "U$15") (pin "3") (pinfunction "GND_3") (pintype "bidirectional"))
      (node (ref "U$15") (pin "4") (pinfunction "GND_4") (pintype "bidirectional"))
      (node (ref "U$15") (pin "5") (pinfunction "GND_5") (pintype "bidirectional"))
      (node (ref "U$15") (pin "6") (pinfunction "GND_6") (pintype "bidirectional"))
      (node (ref "U$15") (pin "7") (pinfunction "GND_7") (pintype "bidirectional"))
      (node (ref "U$15") (pin "8") (pinfunction "GND_8") (pintype "bidirectional"))
      (node (ref "U$16") (pin "3") (pinfunction "GND_3") (pintype "bidirectional"))
      (node (ref "U$16") (pin "4") (pinfunction "GND_4") (pintype "bidirectional"))
      (node (ref "U$16") (pin "5") (pinfunction "GND_5") (pintype "bidirectional"))
      (node (ref "U$16") (pin "6") (pinfunction "GND_6") (pintype "bidirectional"))
      (node (ref "U$16") (pin "7") (pinfunction "GND_7") (pintype "bidirectional"))
      (node (ref "U$16") (pin "8") (pinfunction "GND_8") (pintype "bidirectional"))
      (node (ref "U$17") (pin "3") (pinfunction "GND_3") (pintype "bidirectional"))
      (node (ref "U$17") (pin "4") (pinfunction "GND_4") (pintype "bidirectional"))
      (node (ref "U$17") (pin "5") (pinfunction "GND_5") (pintype "bidirectional"))
      (node (ref "U$17") (pin "6") (pinfunction "GND_6") (pintype "bidirectional"))
      (node (ref "U$17") (pin "7") (pinfunction "GND_7") (pintype "bidirectional"))
      (node (ref "U$17") (pin "8") (pinfunction "GND_8") (pintype "bidirectional"))
      (node (ref "U$18") (pin "3") (pinfunction "GND_3") (pintype "bidirectional"))
      (node (ref "U$18") (pin "4") (pinfunction "GND_4") (pintype "bidirectional"))
      (node (ref "U$18") (pin "5") (pinfunction "GND_5") (pintype "bidirectional"))
      (node (ref "U$18") (pin "6") (pinfunction "GND_6") (pintype "bidirectional"))
      (node (ref "U$18") (pin "7") (pinfunction "GND_7") (pintype "bidirectional"))
      (node (ref "U$18") (pin "8") (pinfunction "GND_8") (pintype "bidirectional"))
      (node (ref "U$19") (pin "2") (pinfunction "2_2") (pintype "bidirectional"))
      (node (ref "U$2") (pin "3") (pinfunction "GND_3") (pintype "bidirectional"))
      (node (ref "U$2") (pin "4") (pinfunction "GND_4") (pintype "bidirectional"))
      (node (ref "U$2") (pin "5") (pinfunction "GND_5") (pintype "bidirectional"))
      (node (ref "U$2") (pin "6") (pinfunction "GND_6") (pintype "bidirectional"))
      (node (ref "U$2") (pin "7") (pinfunction "GND_7") (pintype "bidirectional"))
      (node (ref "U$2") (pin "8") (pinfunction "GND_8") (pintype "bidirectional"))
      (node (ref "U$20") (pin "3") (pinfunction "GND_3") (pintype "bidirectional"))
      (node (ref "U$20") (pin "4") (pinfunction "GND_4") (pintype "bidirectional"))
      (node (ref "U$20") (pin "5") (pinfunction "GND_5") (pintype "bidirectional"))
      (node (ref "U$20") (pin "6") (pinfunction "GND_6") (pintype "bidirectional"))
      (node (ref "U$20") (pin "7") (pinfunction "GND_7") (pintype "bidirectional"))
      (node (ref "U$20") (pin "8") (pinfunction "GND_8") (pintype "bidirectional"))
      (node (ref "U$21") (pin "3") (pinfunction "GND_3") (pintype "bidirectional"))
      (node (ref "U$21") (pin "4") (pinfunction "GND_4") (pintype "bidirectional"))
      (node (ref "U$21") (pin "5") (pinfunction "GND_5") (pintype "bidirectional"))
      (node (ref "U$21") (pin "6") (pinfunction "GND_6") (pintype "bidirectional"))
      (node (ref "U$21") (pin "7") (pinfunction "GND_7") (pintype "bidirectional"))
      (node (ref "U$21") (pin "8") (pinfunction "GND_8") (pintype "bidirectional"))
      (node (ref "U$22") (pin "3") (pinfunction "3_3") (pintype "bidirectional"))
      (node (ref "U$23") (pin "3") (pinfunction "GND_3") (pintype "bidirectional"))
      (node (ref "U$23") (pin "4") (pinfunction "GND_4") (pintype "bidirectional"))
      (node (ref "U$23") (pin "5") (pinfunction "GND_5") (pintype "bidirectional"))
      (node (ref "U$23") (pin "6") (pinfunction "GND_6") (pintype "bidirectional"))
      (node (ref "U$23") (pin "7") (pinfunction "GND_7") (pintype "bidirectional"))
      (node (ref "U$23") (pin "8") (pinfunction "GND_8") (pintype "bidirectional"))
      (node (ref "U$24") (pin "3") (pinfunction "GND_3") (pintype "bidirectional"))
      (node (ref "U$24") (pin "4") (pinfunction "GND_4") (pintype "bidirectional"))
      (node (ref "U$24") (pin "5") (pinfunction "GND_5") (pintype "bidirectional"))
      (node (ref "U$24") (pin "6") (pinfunction "GND_6") (pintype "bidirectional"))
      (node (ref "U$24") (pin "7") (pinfunction "GND_7") (pintype "bidirectional"))
      (node (ref "U$24") (pin "8") (pinfunction "GND_8") (pintype "bidirectional"))
      (node (ref "U$25") (pin "3") (pinfunction "GND_3") (pintype "bidirectional"))
      (node (ref "U$25") (pin "4") (pinfunction "GND_4") (pintype "bidirectional"))
      (node (ref "U$25") (pin "5") (pinfunction "GND_5") (pintype "bidirectional"))
      (node (ref "U$25") (pin "6") (pinfunction "GND_6") (pintype "bidirectional"))
      (node (ref "U$25") (pin "7") (pinfunction "GND_7") (pintype "bidirectional"))
      (node (ref "U$25") (pin "8") (pinfunction "GND_8") (pintype "bidirectional"))
      (node (ref "U$26") (pin "3") (pinfunction "GND_3") (pintype "bidirectional"))
      (node (ref "U$26") (pin "4") (pinfunction "GND_4") (pintype "bidirectional"))
      (node (ref "U$26") (pin "5") (pinfunction "GND_5") (pintype "bidirectional"))
      (node (ref "U$26") (pin "6") (pinfunction "GND_6") (pintype "bidirectional"))
      (node (ref "U$26") (pin "7") (pinfunction "GND_7") (pintype "bidirectional"))
      (node (ref "U$26") (pin "8") (pinfunction "GND_8") (pintype "bidirectional"))
      (node (ref "U$27") (pin "3") (pinfunction "GND_3") (pintype "bidirectional"))
      (node (ref "U$27") (pin "4") (pinfunction "GND_4") (pintype "bidirectional"))
      (node (ref "U$27") (pin "5") (pinfunction "GND_5") (pintype "bidirectional"))
      (node (ref "U$27") (pin "6") (pinfunction "GND_6") (pintype "bidirectional"))
      (node (ref "U$27") (pin "7") (pinfunction "GND_7") (pintype "bidirectional"))
      (node (ref "U$27") (pin "8") (pinfunction "GND_8") (pintype "bidirectional"))
      (node (ref "U$3") (pin "3") (pinfunction "GND_3") (pintype "bidirectional"))
      (node (ref "U$3") (pin "4") (pinfunction "GND_4") (pintype "bidirectional"))
      (node (ref "U$3") (pin "5") (pinfunction "GND_5") (pintype "bidirectional"))
      (node (ref "U$3") (pin "6") (pinfunction "GND_6") (pintype "bidirectional"))
      (node (ref "U$3") (pin "7") (pinfunction "GND_7") (pintype "bidirectional"))
      (node (ref "U$3") (pin "8") (pinfunction "GND_8") (pintype "bidirectional"))
      (node (ref "U$4") (pin "3") (pinfunction "GND_3") (pintype "bidirectional"))
      (node (ref "U$4") (pin "4") (pinfunction "GND_4") (pintype "bidirectional"))
      (node (ref "U$4") (pin "5") (pinfunction "GND_5") (pintype "bidirectional"))
      (node (ref "U$4") (pin "6") (pinfunction "GND_6") (pintype "bidirectional"))
      (node (ref "U$4") (pin "7") (pinfunction "GND_7") (pintype "bidirectional"))
      (node (ref "U$4") (pin "8") (pinfunction "GND_8") (pintype "bidirectional"))
      (node (ref "U$5") (pin "3") (pinfunction "GND_3") (pintype "bidirectional"))
      (node (ref "U$5") (pin "4") (pinfunction "GND_4") (pintype "bidirectional"))
      (node (ref "U$5") (pin "5") (pinfunction "GND_5") (pintype "bidirectional"))
      (node (ref "U$5") (pin "6") (pinfunction "GND_6") (pintype "bidirectional"))
      (node (ref "U$5") (pin "7") (pinfunction "GND_7") (pintype "bidirectional"))
      (node (ref "U$5") (pin "8") (pinfunction "GND_8") (pintype "bidirectional"))
      (node (ref "U$6") (pin "3") (pinfunction "GND_3") (pintype "bidirectional"))
      (node (ref "U$6") (pin "4") (pinfunction "GND_4") (pintype "bidirectional"))
      (node (ref "U$6") (pin "5") (pinfunction "GND_5") (pintype "bidirectional"))
      (node (ref "U$6") (pin "6") (pinfunction "GND_6") (pintype "bidirectional"))
      (node (ref "U$6") (pin "7") (pinfunction "GND_7") (pintype "bidirectional"))
      (node (ref "U$6") (pin "8") (pinfunction "GND_8") (pintype "bidirectional"))
      (node (ref "U$7") (pin "3") (pinfunction "GND_3") (pintype "bidirectional"))
      (node (ref "U$7") (pin "4") (pinfunction "GND_4") (pintype "bidirectional"))
      (node (ref "U$7") (pin "5") (pinfunction "GND_5") (pintype "bidirectional"))
      (node (ref "U$7") (pin "6") (pinfunction "GND_6") (pintype "bidirectional"))
      (node (ref "U$7") (pin "7") (pinfunction "GND_7") (pintype "bidirectional"))
      (node (ref "U$7") (pin "8") (pinfunction "GND_8") (pintype "bidirectional"))
      (node (ref "U$8") (pin "3") (pinfunction "GND_3") (pintype "bidirectional"))
      (node (ref "U$8") (pin "4") (pinfunction "GND_4") (pintype "bidirectional"))
      (node (ref "U$8") (pin "5") (pinfunction "GND_5") (pintype "bidirectional"))
      (node (ref "U$8") (pin "6") (pinfunction "GND_6") (pintype "bidirectional"))
      (node (ref "U$8") (pin "7") (pinfunction "GND_7") (pintype "bidirectional"))
      (node (ref "U$8") (pin "8") (pinfunction "GND_8") (pintype "bidirectional"))
      (node (ref "U$9") (pin "3") (pinfunction "GND_3") (pintype "bidirectional"))
      (node (ref "U$9") (pin "4") (pinfunction "GND_4") (pintype "bidirectional"))
      (node (ref "U$9") (pin "5") (pinfunction "GND_5") (pintype "bidirectional"))
      (node (ref "U$9") (pin "6") (pinfunction "GND_6") (pintype "bidirectional"))
      (node (ref "U$9") (pin "7") (pinfunction "GND_7") (pintype "bidirectional"))
      (node (ref "U$9") (pin "8") (pinfunction "GND_8") (pintype "bidirectional"))
    )
    (net (code "7") (name "Net-(D1-Pad+)") (class "Default")
      (node (ref "D1") (pin "+") (pinfunction "+_+") (pintype "passive"))
      (node (ref "R1") (pin "2") (pinfunction "2_2") (pintype "bidirectional"))
    )
    (net (code "8") (name "Net-(D2-Pad+)") (class "Default")
      (node (ref "D2") (pin "+") (pinfunction "+_+") (pintype "passive"))
      (node (ref "R2") (pin "2") (pinfunction "2_2") (pintype "bidirectional"))
    )
    (net (code "9") (name "Net-(D3-Pad+)") (class "Default")
      (node (ref "D3") (pin "+") (pinfunction "+_+") (pintype "passive"))
      (node (ref "R3") (pin "2") (pinfunction "2_2") (pintype "bidirectional"))
    )
  )
)
